# Button_Mount.net
KiCad netlist of a schematic drawn in EAGLE
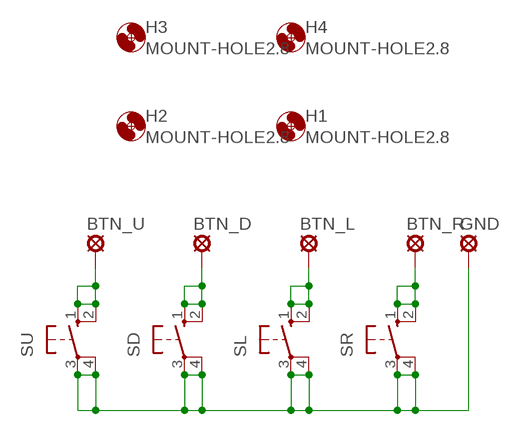
[diagram p0: schematic, sheet 1]

(export (version "E")
  (design (tool "Eeschema 10.0.6"))
  (components
    (comp (ref "BTN_D")
      (value "LSP10")
      (footprint "eagle-import:LSP10")
      (libsource (lib "eagle-import") (part "LSP10"))
    )
    (comp (ref "BTN_L")
      (value "LSP10")
      (footprint "eagle-import:LSP10")
      (libsource (lib "eagle-import") (part "LSP10"))
    )
    (comp (ref "BTN_R")
      (value "LSP10")
      (footprint "eagle-import:LSP10")
      (libsource (lib "eagle-import") (part "LSP10"))
    )
    (comp (ref "BTN_U")
      (value "LSP10")
      (footprint "eagle-import:LSP10")
      (libsource (lib "eagle-import") (part "LSP10"))
    )
    (comp (ref "GND")
      (value "LSP10")
      (footprint "eagle-import:LSP10")
      (libsource (lib "eagle-import") (part "LSP10"))
    )
    (comp (ref "H1")
      (value "MOUNT-HOLE2.8")
      (footprint "eagle-import:2,8")
      (libsource (lib "eagle-import") (part "MOUNT-HOLE2.8"))
    )
    (comp (ref "H2")
      (value "MOUNT-HOLE2.8")
      (footprint "eagle-import:2,8")
      (libsource (lib "eagle-import") (part "MOUNT-HOLE2.8"))
    )
    (comp (ref "H3")
      (value "MOUNT-HOLE2.8")
      (footprint "eagle-import:2,8")
      (libsource (lib "eagle-import") (part "MOUNT-HOLE2.8"))
    )
    (comp (ref "H4")
      (value "MOUNT-HOLE2.8")
      (footprint "eagle-import:2,8")
      (libsource (lib "eagle-import") (part "MOUNT-HOLE2.8"))
    )
    (comp (ref "SD")
      (value "10-XX")
      (footprint "eagle-import:B3F-10XX")
      (fields (field (name "MPN") "B3F-1000"))
      (libsource (lib "eagle-import") (part "10-XX"))
    )
    (comp (ref "SL")
      (value "10-XX")
      (footprint "eagle-import:B3F-10XX")
      (fields (field (name "MPN") "B3F-1000"))
      (libsource (lib "eagle-import") (part "10-XX"))
    )
    (comp (ref "SR")
      (value "10-XX")
      (footprint "eagle-import:B3F-10XX")
      (fields (field (name "MPN") "B3F-1000"))
      (libsource (lib "eagle-import") (part "10-XX"))
    )
    (comp (ref "SU")
      (value "10-XX")
      (footprint "eagle-import:B3F-10XX")
      (fields (field (name "MPN") "B3F-1000"))
      (libsource (lib "eagle-import") (part "10-XX"))
    )
  )
  (nets
    (net (code "1") (name "Net-(SD-P)") (class "Default")
      (node (ref "GND") (pin "MP") (pinfunction "MP_MP") (pintype "passive"))
      (node (ref "SD") (pin "3") (pinfunction "P_3") (pintype "passive"))
      (node (ref "SD") (pin "4") (pinfunction "P1_4") (pintype "passive"))
      (node (ref "SL") (pin "3") (pinfunction "P_3") (pintype "passive"))
      (node (ref "SL") (pin "4") (pinfunction "P1_4") (pintype "passive"))
      (node (ref "SR") (pin "3") (pinfunction "P_3") (pintype "passive"))
      (node (ref "SR") (pin "4") (pinfunction "P1_4") (pintype "passive"))
      (node (ref "SU") (pin "3") (pinfunction "P_3") (pintype "passive"))
      (node (ref "SU") (pin "4") (pinfunction "P1_4") (pintype "passive"))
    )
    (net (code "2") (name "Net-(SD-S)") (class "Default")
      (node (ref "BTN_D") (pin "MP") (pinfunction "MP_MP") (pintype "passive"))
      (node (ref "SD") (pin "1") (pinfunction "S_1") (pintype "passive"))
      (node (ref "SD") (pin "2") (pinfunction "S1_2") (pintype "passive"))
    )
    (net (code "3") (name "Net-(SL-S)") (class "Default")
      (node (ref "BTN_L") (pin "MP") (pinfunction "MP_MP") (pintype "passive"))
      (node (ref "SL") (pin "1") (pinfunction "S_1") (pintype "passive"))
      (node (ref "SL") (pin "2") (pinfunction "S1_2") (pintype "passive"))
    )
    (net (code "4") (name "Net-(SR-S)") (class "Default")
      (node (ref "BTN_R") (pin "MP") (pinfunction "MP_MP") (pintype "passive"))
      (node (ref "SR") (pin "1") (pinfunction "S_1") (pintype "passive"))
      (node (ref "SR") (pin "2") (pinfunction "S1_2") (pintype "passive"))
    )
    (net (code "5") (name "Net-(SU-S)") (class "Default")
      (node (ref "BTN_U") (pin "MP") (pinfunction "MP_MP") (pintype "passive"))
      (node (ref "SU") (pin "1") (pinfunction "S_1") (pintype "passive"))
      (node (ref "SU") (pin "2") (pinfunction "S1_2") (pintype "passive"))
    )
  )
)
